# ControlCommande_Motors.net
KiCad netlist of a schematic drawn in Altium Designer
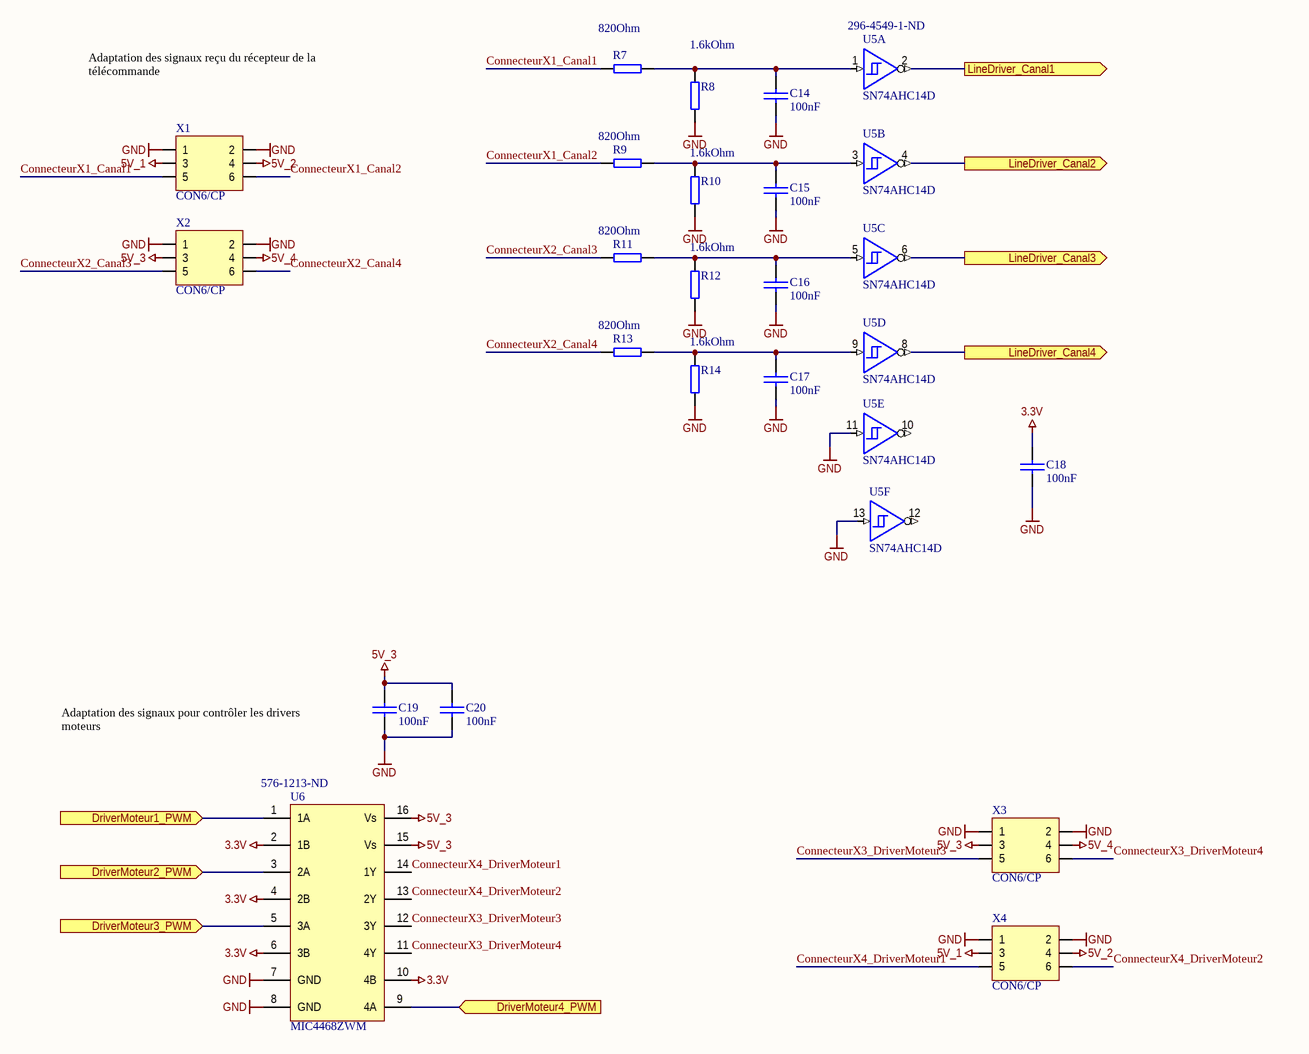
[diagram p0: ControlCommande&Motors.SchDoc]

(export (version "E")
  (design (tool "Eeschema 10.0.6"))
  (components
    (comp (ref "C14")
      (value "100nF")
      (footprint "060301")
      (description "CAPA")
      (fields (field (name "Comment") "GRM188R71E104KA01D"))
      (libsource (lib "General-Sch-205") (part "CAPA"))
    )
    (comp (ref "C15")
      (value "100nF")
      (footprint "060301")
      (description "CAPA")
      (fields (field (name "Comment") "GRM188R71E104KA01D"))
      (libsource (lib "General-Sch-205") (part "CAPA"))
    )
    (comp (ref "C16")
      (value "100nF")
      (footprint "060301")
      (description "CAPA")
      (fields (field (name "Comment") "GRM188R71E104KA01D"))
      (libsource (lib "General-Sch-205") (part "CAPA"))
    )
    (comp (ref "C17")
      (value "100nF")
      (footprint "060301")
      (description "CAPA")
      (fields (field (name "Comment") "GRM188R71E104KA01D"))
      (libsource (lib "General-Sch-205") (part "CAPA"))
    )
    (comp (ref "C18")
      (value "100nF")
      (footprint "060301")
      (description "CAPA")
      (fields (field (name "Comment") "GRM188R71E104KA01D"))
      (libsource (lib "General-Sch-205") (part "CAPA"))
    )
    (comp (ref "C19")
      (value "100nF")
      (footprint "060301")
      (description "CAPA")
      (fields (field (name "Comment") "GRM188R71E104KA01D"))
      (libsource (lib "General-Sch-205") (part "CAPA"))
    )
    (comp (ref "C20")
      (value "100nF")
      (footprint "060301")
      (description "CAPA")
      (fields (field (name "Comment") "GRM188R71E104KA01D"))
      (libsource (lib "General-Sch-205") (part "CAPA"))
    )
    (comp (ref "R7")
      (value "820Ohm")
      (footprint "080501")
      (fields (field (name "Comment") "RMCF0805JT820R"))
      (libsource (lib "General-Sch-205") (part "RES"))
    )
    (comp (ref "R8")
      (value "1.6kOhm")
      (footprint "080501")
      (fields (field (name "Comment") "ERJ-6GEYJ162V"))
      (libsource (lib "General-Sch-205") (part "RES"))
    )
    (comp (ref "R9")
      (value "820Ohm")
      (footprint "080501")
      (fields (field (name "Comment") "RMCF0805JT820R"))
      (libsource (lib "General-Sch-205") (part "RES"))
    )
    (comp (ref "R10")
      (value "1.6kOhm")
      (footprint "080501")
      (fields (field (name "Comment") "ERJ-6GEYJ162V"))
      (libsource (lib "General-Sch-205") (part "RES"))
    )
    (comp (ref "R11")
      (value "820Ohm")
      (footprint "080501")
      (fields (field (name "Comment") "RMCF0805JT820R"))
      (libsource (lib "General-Sch-205") (part "RES"))
    )
    (comp (ref "R12")
      (value "1.6kOhm")
      (footprint "080501")
      (fields (field (name "Comment") "ERJ-6GEYJ162V"))
      (libsource (lib "General-Sch-205") (part "RES"))
    )
    (comp (ref "R13")
      (value "820Ohm")
      (footprint "080501")
      (fields (field (name "Comment") "RMCF0805JT820R"))
      (libsource (lib "General-Sch-205") (part "RES"))
    )
    (comp (ref "R14")
      (value "1.6kOhm")
      (footprint "080501")
      (fields (field (name "Comment") "ERJ-6GEYJ162V"))
      (libsource (lib "General-Sch-205") (part "RES"))
    )
    (comp (ref "U5")
      (value "SN74AHC14D")
      (footprint "SO1401")
      (fields (field (name "SUPPLIER PART NUMBER 1") "296-4549-1-ND"))
      (libsource (lib "EISI") (part "SN74AHC14D"))
    )
    (comp (ref "U6")
      (value "MIC4468ZWM")
      (footprint "SOIC127P1030-16M")
      (fields (field (name "SUPPLIER PART NUMBER 1") "576-1213-ND"))
      (libsource (lib "Schlib1") (part "MIC4468"))
    )
    (comp (ref "X1")
      (value "CON6/CP")
      (footprint "J2X3_2.54")
      (description "Connecteur récepteur télécommande cannaux 1 & 2")
      (libsource (lib "General-Sch-205") (part "CON6/CP"))
    )
    (comp (ref "X2")
      (value "CON6/CP")
      (footprint "J2X3_2.54")
      (description "Connecteur récepteur télécommande cannaux 3 & 4")
      (libsource (lib "General-Sch-205") (part "CON6/CP"))
    )
    (comp (ref "X3")
      (value "CON6/CP")
      (footprint "J2X3_2.54")
      (description "Connecteur contrôleur moteurs 3 (arrière) & 4 (gauche)")
      (libsource (lib "General-Sch-205") (part "CON6/CP"))
    )
    (comp (ref "X4")
      (value "CON6/CP")
      (footprint "J2X3_2.54")
      (description "Connecteur contrôleur moteurs 1 (avant) & 2 (droite)")
      (libsource (lib "General-Sch-205") (part "CON6/CP"))
    )
  )
  (nets
    (net (code "1") (name "/ConnecteurX1_Canal1") (class "Default")
      (node (ref "R7") (pin "1") (pintype "passive"))
      (node (ref "X1") (pin "5") (pinfunction "5_5") (pintype "passive"))
    )
    (net (code "2") (name "/ConnecteurX1_Canal2") (class "Default")
      (node (ref "R9") (pin "1") (pintype "passive"))
      (node (ref "X1") (pin "6") (pinfunction "6_6") (pintype "passive"))
    )
    (net (code "3") (name "/ConnecteurX2_Canal3") (class "Default")
      (node (ref "R11") (pin "1") (pintype "passive"))
      (node (ref "X2") (pin "5") (pinfunction "5_5") (pintype "passive"))
    )
    (net (code "4") (name "/ConnecteurX2_Canal4") (class "Default")
      (node (ref "R13") (pin "1") (pintype "passive"))
      (node (ref "X2") (pin "6") (pinfunction "6_6") (pintype "passive"))
    )
    (net (code "5") (name "/ConnecteurX3_DriverMoteur3") (class "Default")
      (node (ref "U6") (pin "12") (pinfunction "3Y_12") (pintype "passive"))
      (node (ref "X3") (pin "5") (pinfunction "5_5") (pintype "passive"))
    )
    (net (code "6") (name "/ConnecteurX3_DriverMoteur4") (class "Default")
      (node (ref "U6") (pin "11") (pinfunction "4Y_11") (pintype "passive"))
      (node (ref "X3") (pin "6") (pinfunction "6_6") (pintype "passive"))
    )
    (net (code "7") (name "/ConnecteurX4_DriverMoteur1") (class "Default")
      (node (ref "U6") (pin "14") (pinfunction "1Y_14") (pintype "passive"))
      (node (ref "X4") (pin "5") (pinfunction "5_5") (pintype "passive"))
    )
    (net (code "8") (name "/ConnecteurX4_DriverMoteur2") (class "Default")
      (node (ref "U6") (pin "13") (pinfunction "2Y_13") (pintype "passive"))
      (node (ref "X4") (pin "6") (pinfunction "6_6") (pintype "passive"))
    )
    (net (code "9") (name "/DriverMoteur1_PWM") (class "Default")
      (node (ref "U6") (pin "1") (pinfunction "1A_1") (pintype "passive"))
    )
    (net (code "10") (name "/DriverMoteur2_PWM") (class "Default")
      (node (ref "U6") (pin "3") (pinfunction "2A_3") (pintype "passive"))
    )
    (net (code "11") (name "/DriverMoteur3_PWM") (class "Default")
      (node (ref "U6") (pin "5") (pinfunction "3A_5") (pintype "passive"))
    )
    (net (code "12") (name "/DriverMoteur4_PWM") (class "Default")
      (node (ref "U6") (pin "9") (pinfunction "4A_9") (pintype "passive"))
    )
    (net (code "13") (name "/LineDriver_Canal1") (class "Default")
      (node (ref "U5") (pin "2") (pinfunction "2_2") (pintype "output"))
    )
    (net (code "14") (name "/LineDriver_Canal2") (class "Default")
      (node (ref "U5") (pin "4") (pinfunction "4_4") (pintype "output"))
    )
    (net (code "15") (name "/LineDriver_Canal3") (class "Default")
      (node (ref "U5") (pin "6") (pinfunction "6_6") (pintype "output"))
    )
    (net (code "16") (name "/LineDriver_Canal4") (class "Default")
      (node (ref "U5") (pin "8") (pinfunction "8_8") (pintype "output"))
    )
    (net (code "17") (name "3.3V") (class "Default")
      (node (ref "C18") (pin "1") (pintype "passive"))
      (node (ref "U5") (pin "14") (pinfunction "3.3V_14") (pintype "power_in"))
      (node (ref "U6") (pin "10") (pinfunction "4B_10") (pintype "passive"))
      (node (ref "U6") (pin "2") (pinfunction "1B_2") (pintype "passive"))
      (node (ref "U6") (pin "4") (pinfunction "2B_4") (pintype "passive"))
      (node (ref "U6") (pin "6") (pinfunction "3B_6") (pintype "passive"))
    )
    (net (code "18") (name "5V_1") (class "Default")
      (node (ref "X1") (pin "3") (pinfunction "3_3") (pintype "passive"))
      (node (ref "X4") (pin "3") (pinfunction "3_3") (pintype "passive"))
    )
    (net (code "19") (name "5V_2") (class "Default")
      (node (ref "X1") (pin "4") (pinfunction "4_4") (pintype "passive"))
      (node (ref "X4") (pin "4") (pinfunction "4_4") (pintype "passive"))
    )
    (net (code "20") (name "5V_3") (class "Default")
      (node (ref "C19") (pin "1") (pintype "passive"))
      (node (ref "C20") (pin "1") (pintype "passive"))
      (node (ref "U6") (pin "15") (pinfunction "Vs_15") (pintype "passive"))
      (node (ref "U6") (pin "16") (pinfunction "Vs_16") (pintype "passive"))
      (node (ref "X2") (pin "3") (pinfunction "3_3") (pintype "passive"))
      (node (ref "X3") (pin "3") (pinfunction "3_3") (pintype "passive"))
    )
    (net (code "21") (name "5V_4") (class "Default")
      (node (ref "X2") (pin "4") (pinfunction "4_4") (pintype "passive"))
      (node (ref "X3") (pin "4") (pinfunction "4_4") (pintype "passive"))
    )
    (net (code "22") (name "GND") (class "Default")
      (node (ref "C14") (pin "2") (pintype "passive"))
      (node (ref "C15") (pin "2") (pintype "passive"))
      (node (ref "C16") (pin "2") (pintype "passive"))
      (node (ref "C17") (pin "2") (pintype "passive"))
      (node (ref "C18") (pin "2") (pintype "passive"))
      (node (ref "C19") (pin "2") (pintype "passive"))
      (node (ref "C20") (pin "2") (pintype "passive"))
      (node (ref "R10") (pin "2") (pintype "passive"))
      (node (ref "R12") (pin "2") (pintype "passive"))
      (node (ref "R14") (pin "2") (pintype "passive"))
      (node (ref "R8") (pin "2") (pintype "passive"))
      (node (ref "U5") (pin "11") (pinfunction "11_11") (pintype "input"))
      (node (ref "U5") (pin "13") (pinfunction "13_13") (pintype "input"))
      (node (ref "U5") (pin "7") (pinfunction "GND_7") (pintype "power_in"))
      (node (ref "U6") (pin "7") (pinfunction "GND_7") (pintype "passive"))
      (node (ref "U6") (pin "8") (pinfunction "GND_8") (pintype "passive"))
      (node (ref "X1") (pin "1") (pinfunction "1_1") (pintype "passive"))
      (node (ref "X1") (pin "2") (pinfunction "2_2") (pintype "passive"))
      (node (ref "X2") (pin "1") (pinfunction "1_1") (pintype "passive"))
      (node (ref "X2") (pin "2") (pinfunction "2_2") (pintype "passive"))
      (node (ref "X3") (pin "1") (pinfunction "1_1") (pintype "passive"))
      (node (ref "X3") (pin "2") (pinfunction "2_2") (pintype "passive"))
      (node (ref "X4") (pin "1") (pinfunction "1_1") (pintype "passive"))
      (node (ref "X4") (pin "2") (pinfunction "2_2") (pintype "passive"))
    )
    (net (code "23") (name "Net-(C14-Pad1)") (class "Default")
      (node (ref "C14") (pin "1") (pintype "passive"))
      (node (ref "R7") (pin "2") (pintype "passive"))
      (node (ref "R8") (pin "1") (pintype "passive"))
      (node (ref "U5") (pin "1") (pinfunction "1_1") (pintype "input"))
    )
    (net (code "24") (name "Net-(C15-Pad1)") (class "Default")
      (node (ref "C15") (pin "1") (pintype "passive"))
      (node (ref "R10") (pin "1") (pintype "passive"))
      (node (ref "R9") (pin "2") (pintype "passive"))
      (node (ref "U5") (pin "3") (pinfunction "3_3") (pintype "input"))
    )
    (net (code "25") (name "Net-(C16-Pad1)") (class "Default")
      (node (ref "C16") (pin "1") (pintype "passive"))
      (node (ref "R11") (pin "2") (pintype "passive"))
      (node (ref "R12") (pin "1") (pintype "passive"))
      (node (ref "U5") (pin "5") (pinfunction "5_5") (pintype "input"))
    )
    (net (code "26") (name "Net-(C17-Pad1)") (class "Default")
      (node (ref "C17") (pin "1") (pintype "passive"))
      (node (ref "R13") (pin "2") (pintype "passive"))
      (node (ref "R14") (pin "1") (pintype "passive"))
      (node (ref "U5") (pin "9") (pinfunction "9_9") (pintype "input"))
    )
    (net (code "27") (name "unconnected-(U5-Pad10)") (class "Default")
      (node (ref "U5") (pin "10") (pinfunction "10_10") (pintype "output"))
    )
    (net (code "28") (name "unconnected-(U5-Pad12)") (class "Default")
      (node (ref "U5") (pin "12") (pinfunction "12_12") (pintype "output"))
    )
  )
)
